# PreAmplicationFilteringCircuit.net
KiCad netlist of a schematic drawn in Altium Designer
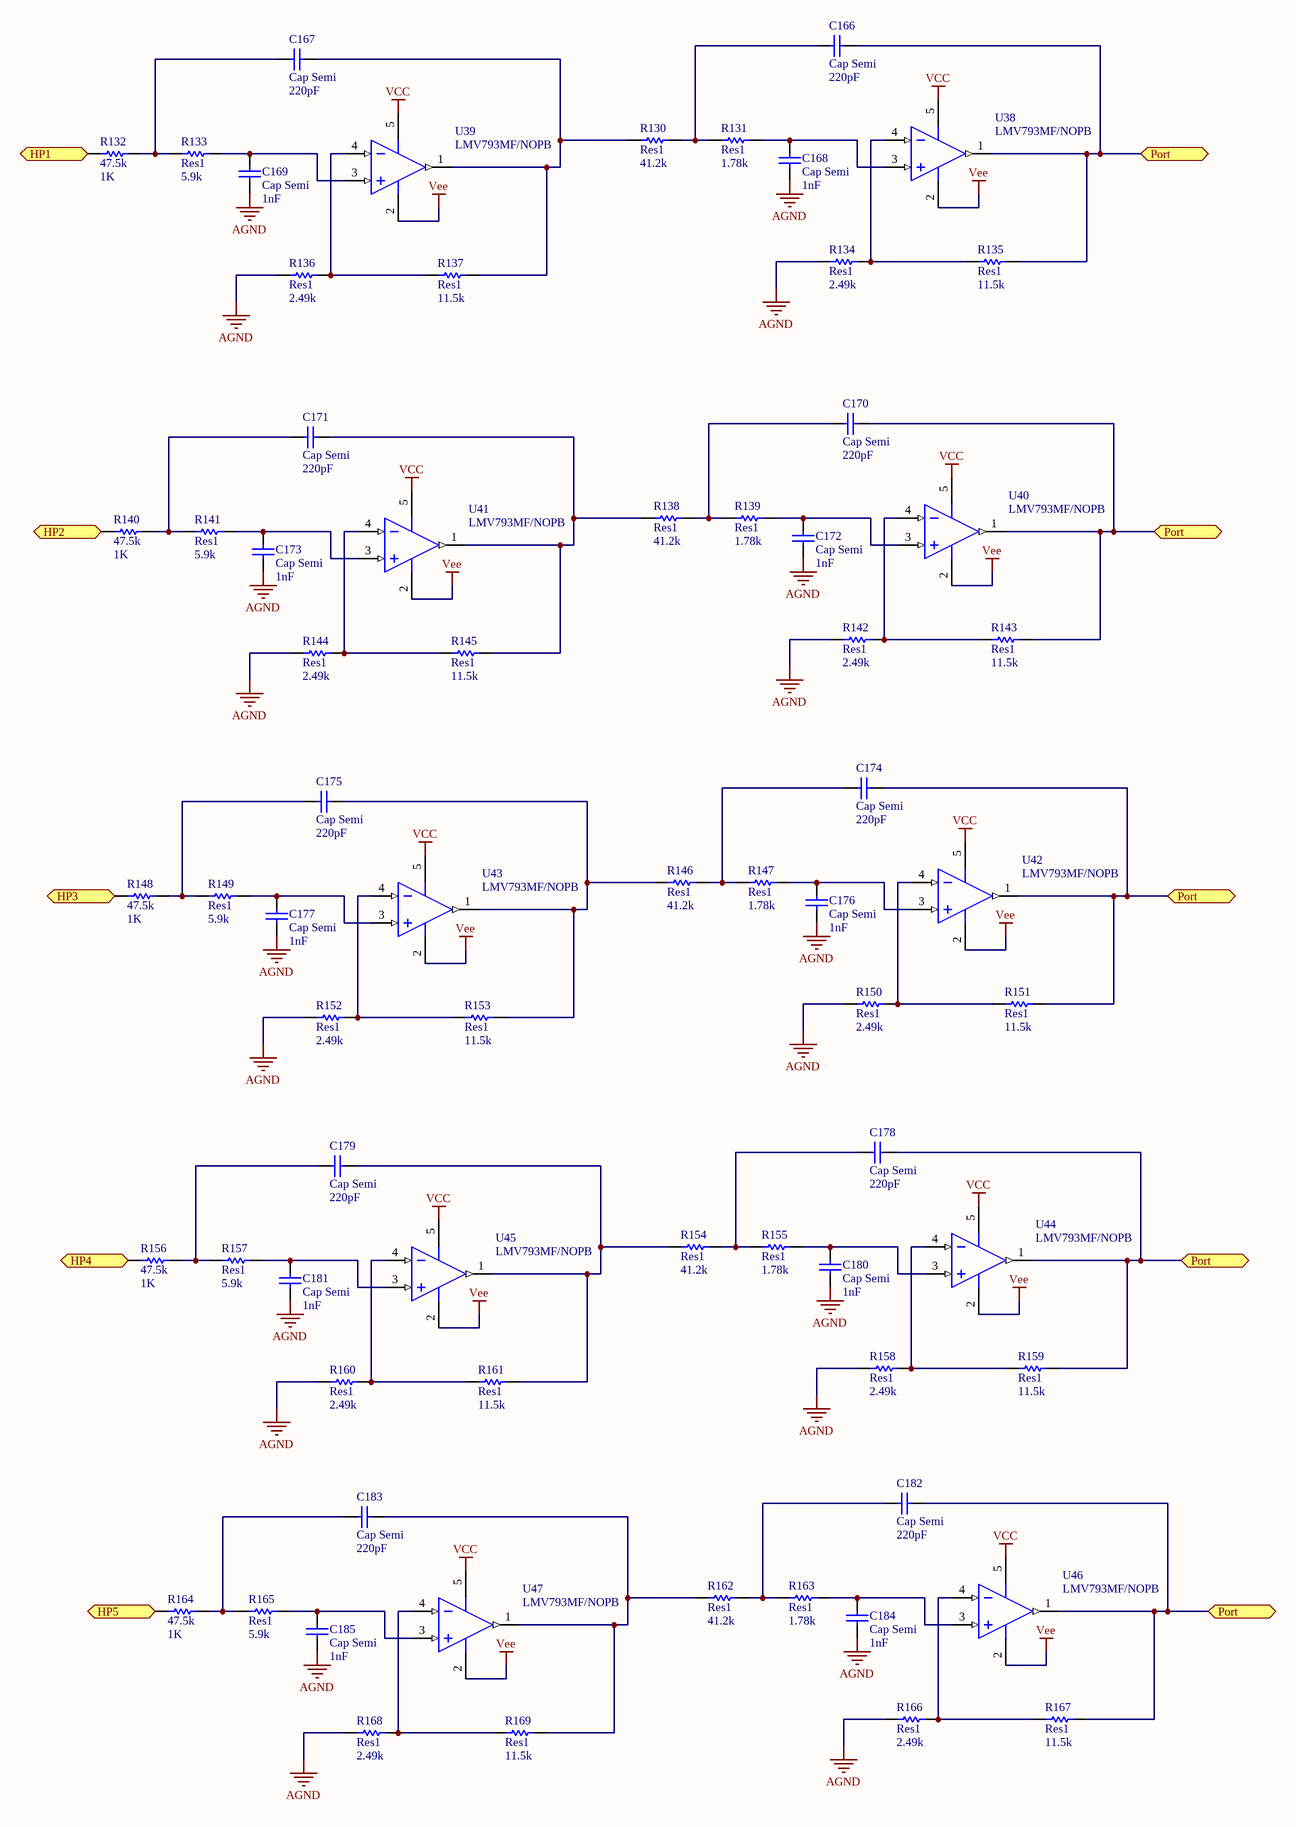
[diagram p0: PreAmplicationFilteringCircuit.SchDoc]

(export (version "E")
  (design (tool "Eeschema 10.0.6"))
  (components
    (comp (ref "C166")
      (value "Cap Semi")
      (footprint "0402")
      (description "Capacitor (Semiconductor SIM Model)")
      (fields (field (name "ALTIUM_VALUE") "220pF") (field (name "PUBLISHER") "Altium Limited"))
      (libsource (lib "Miscellaneous Devices") (part "Cap Semi"))
    )
    (comp (ref "C167")
      (value "Cap Semi")
      (footprint "0402")
      (description "Capacitor (Semiconductor SIM Model)")
      (fields (field (name "ALTIUM_VALUE") "220pF") (field (name "PUBLISHER") "Altium Limited"))
      (libsource (lib "Miscellaneous Devices") (part "Cap Semi"))
    )
    (comp (ref "C168")
      (value "Cap Semi")
      (footprint "0402")
      (description "Capacitor (Semiconductor SIM Model)")
      (fields (field (name "ALTIUM_VALUE") "1nF") (field (name "PUBLISHER") "Altium Limited"))
      (libsource (lib "Miscellaneous Devices") (part "Cap Semi"))
    )
    (comp (ref "C169")
      (value "Cap Semi")
      (footprint "0402")
      (description "Capacitor (Semiconductor SIM Model)")
      (fields (field (name "ALTIUM_VALUE") "1nF") (field (name "PUBLISHER") "Altium Limited"))
      (libsource (lib "Miscellaneous Devices") (part "Cap Semi"))
    )
    (comp (ref "C170")
      (value "Cap Semi")
      (footprint "0402")
      (description "Capacitor (Semiconductor SIM Model)")
      (fields (field (name "ALTIUM_VALUE") "220pF") (field (name "PUBLISHER") "Altium Limited"))
      (libsource (lib "Miscellaneous Devices") (part "Cap Semi"))
    )
    (comp (ref "C171")
      (value "Cap Semi")
      (footprint "0402")
      (description "Capacitor (Semiconductor SIM Model)")
      (fields (field (name "ALTIUM_VALUE") "220pF") (field (name "PUBLISHER") "Altium Limited"))
      (libsource (lib "Miscellaneous Devices") (part "Cap Semi"))
    )
    (comp (ref "C172")
      (value "Cap Semi")
      (footprint "0402")
      (description "Capacitor (Semiconductor SIM Model)")
      (fields (field (name "ALTIUM_VALUE") "1nF") (field (name "PUBLISHER") "Altium Limited"))
      (libsource (lib "Miscellaneous Devices") (part "Cap Semi"))
    )
    (comp (ref "C173")
      (value "Cap Semi")
      (footprint "0402")
      (description "Capacitor (Semiconductor SIM Model)")
      (fields (field (name "ALTIUM_VALUE") "1nF") (field (name "PUBLISHER") "Altium Limited"))
      (libsource (lib "Miscellaneous Devices") (part "Cap Semi"))
    )
    (comp (ref "C174")
      (value "Cap Semi")
      (footprint "0402")
      (description "Capacitor (Semiconductor SIM Model)")
      (fields (field (name "ALTIUM_VALUE") "220pF") (field (name "PUBLISHER") "Altium Limited"))
      (libsource (lib "Miscellaneous Devices") (part "Cap Semi"))
    )
    (comp (ref "C175")
      (value "Cap Semi")
      (footprint "0402")
      (description "Capacitor (Semiconductor SIM Model)")
      (fields (field (name "ALTIUM_VALUE") "220pF") (field (name "PUBLISHER") "Altium Limited"))
      (libsource (lib "Miscellaneous Devices") (part "Cap Semi"))
    )
    (comp (ref "C176")
      (value "Cap Semi")
      (footprint "0402")
      (description "Capacitor (Semiconductor SIM Model)")
      (fields (field (name "ALTIUM_VALUE") "1nF") (field (name "PUBLISHER") "Altium Limited"))
      (libsource (lib "Miscellaneous Devices") (part "Cap Semi"))
    )
    (comp (ref "C177")
      (value "Cap Semi")
      (footprint "0402")
      (description "Capacitor (Semiconductor SIM Model)")
      (fields (field (name "ALTIUM_VALUE") "1nF") (field (name "PUBLISHER") "Altium Limited"))
      (libsource (lib "Miscellaneous Devices") (part "Cap Semi"))
    )
    (comp (ref "C178")
      (value "Cap Semi")
      (footprint "0402")
      (description "Capacitor (Semiconductor SIM Model)")
      (fields (field (name "ALTIUM_VALUE") "220pF") (field (name "PUBLISHER") "Altium Limited"))
      (libsource (lib "Miscellaneous Devices") (part "Cap Semi"))
    )
    (comp (ref "C179")
      (value "Cap Semi")
      (footprint "0402")
      (description "Capacitor (Semiconductor SIM Model)")
      (fields (field (name "ALTIUM_VALUE") "220pF") (field (name "PUBLISHER") "Altium Limited"))
      (libsource (lib "Miscellaneous Devices") (part "Cap Semi"))
    )
    (comp (ref "C180")
      (value "Cap Semi")
      (footprint "0402")
      (description "Capacitor (Semiconductor SIM Model)")
      (fields (field (name "ALTIUM_VALUE") "1nF") (field (name "PUBLISHER") "Altium Limited"))
      (libsource (lib "Miscellaneous Devices") (part "Cap Semi"))
    )
    (comp (ref "C181")
      (value "Cap Semi")
      (footprint "0402")
      (description "Capacitor (Semiconductor SIM Model)")
      (fields (field (name "ALTIUM_VALUE") "1nF") (field (name "PUBLISHER") "Altium Limited"))
      (libsource (lib "Miscellaneous Devices") (part "Cap Semi"))
    )
    (comp (ref "C182")
      (value "Cap Semi")
      (footprint "0402")
      (description "Capacitor (Semiconductor SIM Model)")
      (fields (field (name "ALTIUM_VALUE") "220pF") (field (name "PUBLISHER") "Altium Limited"))
      (libsource (lib "Miscellaneous Devices") (part "Cap Semi"))
    )
    (comp (ref "C183")
      (value "Cap Semi")
      (footprint "0402")
      (description "Capacitor (Semiconductor SIM Model)")
      (fields (field (name "ALTIUM_VALUE") "220pF") (field (name "PUBLISHER") "Altium Limited"))
      (libsource (lib "Miscellaneous Devices") (part "Cap Semi"))
    )
    (comp (ref "C184")
      (value "Cap Semi")
      (footprint "0402")
      (description "Capacitor (Semiconductor SIM Model)")
      (fields (field (name "ALTIUM_VALUE") "1nF") (field (name "PUBLISHER") "Altium Limited"))
      (libsource (lib "Miscellaneous Devices") (part "Cap Semi"))
    )
    (comp (ref "C185")
      (value "Cap Semi")
      (footprint "0402")
      (description "Capacitor (Semiconductor SIM Model)")
      (fields (field (name "ALTIUM_VALUE") "1nF") (field (name "PUBLISHER") "Altium Limited"))
      (libsource (lib "Miscellaneous Devices") (part "Cap Semi"))
    )
    (comp (ref "R130")
      (value "Res1")
      (footprint "AXIAL-0.3")
      (description "Resistor")
      (fields (field (name "ALTIUM_VALUE") "41.2k") (field (name "PUBLISHER") "Altium Limited"))
      (libsource (lib "Miscellaneous Devices") (part "Res1"))
    )
    (comp (ref "R131")
      (value "Res1")
      (footprint "AXIAL-0.3")
      (description "Resistor")
      (fields (field (name "ALTIUM_VALUE") "1.78k") (field (name "PUBLISHER") "Altium Limited"))
      (libsource (lib "Miscellaneous Devices") (part "Res1"))
    )
    (comp (ref "R132")
      (value "47.5k")
      (footprint "AXIAL-0.3")
      (description "Resistor")
      (fields (field (name "ALTIUM_VALUE") "1K") (field (name "PUBLISHER") "Altium Limited"))
      (libsource (lib "Miscellaneous Devices") (part "Res1"))
    )
    (comp (ref "R133")
      (value "Res1")
      (footprint "AXIAL-0.3")
      (description "Resistor")
      (fields (field (name "ALTIUM_VALUE") "5.9k") (field (name "PUBLISHER") "Altium Limited"))
      (libsource (lib "Miscellaneous Devices") (part "Res1"))
    )
    (comp (ref "R134")
      (value "Res1")
      (footprint "AXIAL-0.3")
      (description "Resistor")
      (fields (field (name "ALTIUM_VALUE") "2.49k") (field (name "PUBLISHER") "Altium Limited"))
      (libsource (lib "Miscellaneous Devices") (part "Res1"))
    )
    (comp (ref "R135")
      (value "Res1")
      (footprint "AXIAL-0.3")
      (description "Resistor")
      (fields (field (name "ALTIUM_VALUE") "11.5k") (field (name "PUBLISHER") "Altium Limited"))
      (libsource (lib "Miscellaneous Devices") (part "Res1"))
    )
    (comp (ref "R136")
      (value "Res1")
      (footprint "AXIAL-0.3")
      (description "Resistor")
      (fields (field (name "ALTIUM_VALUE") "2.49k") (field (name "PUBLISHER") "Altium Limited"))
      (libsource (lib "Miscellaneous Devices") (part "Res1"))
    )
    (comp (ref "R137")
      (value "Res1")
      (footprint "AXIAL-0.3")
      (description "Resistor")
      (fields (field (name "ALTIUM_VALUE") "11.5k") (field (name "PUBLISHER") "Altium Limited"))
      (libsource (lib "Miscellaneous Devices") (part "Res1"))
    )
    (comp (ref "R138")
      (value "Res1")
      (footprint "AXIAL-0.3")
      (description "Resistor")
      (fields (field (name "ALTIUM_VALUE") "41.2k") (field (name "PUBLISHER") "Altium Limited"))
      (libsource (lib "Miscellaneous Devices") (part "Res1"))
    )
    (comp (ref "R139")
      (value "Res1")
      (footprint "AXIAL-0.3")
      (description "Resistor")
      (fields (field (name "ALTIUM_VALUE") "1.78k") (field (name "PUBLISHER") "Altium Limited"))
      (libsource (lib "Miscellaneous Devices") (part "Res1"))
    )
    (comp (ref "R140")
      (value "47.5k")
      (footprint "AXIAL-0.3")
      (description "Resistor")
      (fields (field (name "ALTIUM_VALUE") "1K") (field (name "PUBLISHER") "Altium Limited"))
      (libsource (lib "Miscellaneous Devices") (part "Res1"))
    )
    (comp (ref "R141")
      (value "Res1")
      (footprint "AXIAL-0.3")
      (description "Resistor")
      (fields (field (name "ALTIUM_VALUE") "5.9k") (field (name "PUBLISHER") "Altium Limited"))
      (libsource (lib "Miscellaneous Devices") (part "Res1"))
    )
    (comp (ref "R142")
      (value "Res1")
      (footprint "AXIAL-0.3")
      (description "Resistor")
      (fields (field (name "ALTIUM_VALUE") "2.49k") (field (name "PUBLISHER") "Altium Limited"))
      (libsource (lib "Miscellaneous Devices") (part "Res1"))
    )
    (comp (ref "R143")
      (value "Res1")
      (footprint "AXIAL-0.3")
      (description "Resistor")
      (fields (field (name "ALTIUM_VALUE") "11.5k") (field (name "PUBLISHER") "Altium Limited"))
      (libsource (lib "Miscellaneous Devices") (part "Res1"))
    )
    (comp (ref "R144")
      (value "Res1")
      (footprint "AXIAL-0.3")
      (description "Resistor")
      (fields (field (name "ALTIUM_VALUE") "2.49k") (field (name "PUBLISHER") "Altium Limited"))
      (libsource (lib "Miscellaneous Devices") (part "Res1"))
    )
    (comp (ref "R145")
      (value "Res1")
      (footprint "AXIAL-0.3")
      (description "Resistor")
      (fields (field (name "ALTIUM_VALUE") "11.5k") (field (name "PUBLISHER") "Altium Limited"))
      (libsource (lib "Miscellaneous Devices") (part "Res1"))
    )
    (comp (ref "R146")
      (value "Res1")
      (footprint "AXIAL-0.3")
      (description "Resistor")
      (fields (field (name "ALTIUM_VALUE") "41.2k") (field (name "PUBLISHER") "Altium Limited"))
      (libsource (lib "Miscellaneous Devices") (part "Res1"))
    )
    (comp (ref "R147")
      (value "Res1")
      (footprint "AXIAL-0.3")
      (description "Resistor")
      (fields (field (name "ALTIUM_VALUE") "1.78k") (field (name "PUBLISHER") "Altium Limited"))
      (libsource (lib "Miscellaneous Devices") (part "Res1"))
    )
    (comp (ref "R148")
      (value "47.5k")
      (footprint "AXIAL-0.3")
      (description "Resistor")
      (fields (field (name "ALTIUM_VALUE") "1K") (field (name "PUBLISHER") "Altium Limited"))
      (libsource (lib "Miscellaneous Devices") (part "Res1"))
    )
    (comp (ref "R149")
      (value "Res1")
      (footprint "AXIAL-0.3")
      (description "Resistor")
      (fields (field (name "ALTIUM_VALUE") "5.9k") (field (name "PUBLISHER") "Altium Limited"))
      (libsource (lib "Miscellaneous Devices") (part "Res1"))
    )
    (comp (ref "R150")
      (value "Res1")
      (footprint "AXIAL-0.3")
      (description "Resistor")
      (fields (field (name "ALTIUM_VALUE") "2.49k") (field (name "PUBLISHER") "Altium Limited"))
      (libsource (lib "Miscellaneous Devices") (part "Res1"))
    )
    (comp (ref "R151")
      (value "Res1")
      (footprint "AXIAL-0.3")
      (description "Resistor")
      (fields (field (name "ALTIUM_VALUE") "11.5k") (field (name "PUBLISHER") "Altium Limited"))
      (libsource (lib "Miscellaneous Devices") (part "Res1"))
    )
    (comp (ref "R152")
      (value "Res1")
      (footprint "AXIAL-0.3")
      (description "Resistor")
      (fields (field (name "ALTIUM_VALUE") "2.49k") (field (name "PUBLISHER") "Altium Limited"))
      (libsource (lib "Miscellaneous Devices") (part "Res1"))
    )
    (comp (ref "R153")
      (value "Res1")
      (footprint "AXIAL-0.3")
      (description "Resistor")
      (fields (field (name "ALTIUM_VALUE") "11.5k") (field (name "PUBLISHER") "Altium Limited"))
      (libsource (lib "Miscellaneous Devices") (part "Res1"))
    )
    (comp (ref "R154")
      (value "Res1")
      (footprint "AXIAL-0.3")
      (description "Resistor")
      (fields (field (name "ALTIUM_VALUE") "41.2k") (field (name "PUBLISHER") "Altium Limited"))
      (libsource (lib "Miscellaneous Devices") (part "Res1"))
    )
    (comp (ref "R155")
      (value "Res1")
      (footprint "AXIAL-0.3")
      (description "Resistor")
      (fields (field (name "ALTIUM_VALUE") "1.78k") (field (name "PUBLISHER") "Altium Limited"))
      (libsource (lib "Miscellaneous Devices") (part "Res1"))
    )
    (comp (ref "R156")
      (value "47.5k")
      (footprint "AXIAL-0.3")
      (description "Resistor")
      (fields (field (name "ALTIUM_VALUE") "1K") (field (name "PUBLISHER") "Altium Limited"))
      (libsource (lib "Miscellaneous Devices") (part "Res1"))
    )
    (comp (ref "R157")
      (value "Res1")
      (footprint "AXIAL-0.3")
      (description "Resistor")
      (fields (field (name "ALTIUM_VALUE") "5.9k") (field (name "PUBLISHER") "Altium Limited"))
      (libsource (lib "Miscellaneous Devices") (part "Res1"))
    )
    (comp (ref "R158")
      (value "Res1")
      (footprint "AXIAL-0.3")
      (description "Resistor")
      (fields (field (name "ALTIUM_VALUE") "2.49k") (field (name "PUBLISHER") "Altium Limited"))
      (libsource (lib "Miscellaneous Devices") (part "Res1"))
    )
    (comp (ref "R159")
      (value "Res1")
      (footprint "AXIAL-0.3")
      (description "Resistor")
      (fields (field (name "ALTIUM_VALUE") "11.5k") (field (name "PUBLISHER") "Altium Limited"))
      (libsource (lib "Miscellaneous Devices") (part "Res1"))
    )
    (comp (ref "R160")
      (value "Res1")
      (footprint "AXIAL-0.3")
      (description "Resistor")
      (fields (field (name "ALTIUM_VALUE") "2.49k") (field (name "PUBLISHER") "Altium Limited"))
      (libsource (lib "Miscellaneous Devices") (part "Res1"))
    )
    (comp (ref "R161")
      (value "Res1")
      (footprint "AXIAL-0.3")
      (description "Resistor")
      (fields (field (name "ALTIUM_VALUE") "11.5k") (field (name "PUBLISHER") "Altium Limited"))
      (libsource (lib "Miscellaneous Devices") (part "Res1"))
    )
    (comp (ref "R162")
      (value "Res1")
      (footprint "AXIAL-0.3")
      (description "Resistor")
      (fields (field (name "ALTIUM_VALUE") "41.2k") (field (name "PUBLISHER") "Altium Limited"))
      (libsource (lib "Miscellaneous Devices") (part "Res1"))
    )
    (comp (ref "R163")
      (value "Res1")
      (footprint "AXIAL-0.3")
      (description "Resistor")
      (fields (field (name "ALTIUM_VALUE") "1.78k") (field (name "PUBLISHER") "Altium Limited"))
      (libsource (lib "Miscellaneous Devices") (part "Res1"))
    )
    (comp (ref "R164")
      (value "47.5k")
      (footprint "AXIAL-0.3")
      (description "Resistor")
      (fields (field (name "ALTIUM_VALUE") "1K") (field (name "PUBLISHER") "Altium Limited"))
      (libsource (lib "Miscellaneous Devices") (part "Res1"))
    )
    (comp (ref "R165")
      (value "Res1")
      (footprint "AXIAL-0.3")
      (description "Resistor")
      (fields (field (name "ALTIUM_VALUE") "5.9k") (field (name "PUBLISHER") "Altium Limited"))
      (libsource (lib "Miscellaneous Devices") (part "Res1"))
    )
    (comp (ref "R166")
      (value "Res1")
      (footprint "AXIAL-0.3")
      (description "Resistor")
      (fields (field (name "ALTIUM_VALUE") "2.49k") (field (name "PUBLISHER") "Altium Limited"))
      (libsource (lib "Miscellaneous Devices") (part "Res1"))
    )
    (comp (ref "R167")
      (value "Res1")
      (footprint "AXIAL-0.3")
      (description "Resistor")
      (fields (field (name "ALTIUM_VALUE") "11.5k") (field (name "PUBLISHER") "Altium Limited"))
      (libsource (lib "Miscellaneous Devices") (part "Res1"))
    )
    (comp (ref "R168")
      (value "Res1")
      (footprint "AXIAL-0.3")
      (description "Resistor")
      (fields (field (name "ALTIUM_VALUE") "2.49k") (field (name "PUBLISHER") "Altium Limited"))
      (libsource (lib "Miscellaneous Devices") (part "Res1"))
    )
    (comp (ref "R169")
      (value "Res1")
      (footprint "AXIAL-0.3")
      (description "Resistor")
      (fields (field (name "ALTIUM_VALUE") "11.5k") (field (name "PUBLISHER") "Altium Limited"))
      (libsource (lib "Miscellaneous Devices") (part "Res1"))
    )
    (comp (ref "U38")
      (value "LMV793MF/NOPB")
      (footprint "DBV0005A_N")
      (description "88 MHz, Low Noise, 1.8V CMOS Input, Decompensated Operational Amplifiers, 5-pin SOT-23, Pb-Free")
      (fields (field (name "MANUFACTURER") "Texas Instruments"))
      (libsource (lib "Altium Content Vault") (part "AMP-OPA-LM7121-5"))
    )
    (comp (ref "U39")
      (value "LMV793MF/NOPB")
      (footprint "DBV0005A_N")
      (description "88 MHz, Low Noise, 1.8V CMOS Input, Decompensated Operational Amplifiers, 5-pin SOT-23, Pb-Free")
      (fields (field (name "MANUFACTURER") "Texas Instruments"))
      (libsource (lib "Altium Content Vault") (part "AMP-OPA-LM7121-5"))
    )
    (comp (ref "U40")
      (value "LMV793MF/NOPB")
      (footprint "DBV0005A_N")
      (description "88 MHz, Low Noise, 1.8V CMOS Input, Decompensated Operational Amplifiers, 5-pin SOT-23, Pb-Free")
      (fields (field (name "MANUFACTURER") "Texas Instruments"))
      (libsource (lib "Altium Content Vault") (part "AMP-OPA-LM7121-5"))
    )
    (comp (ref "U41")
      (value "LMV793MF/NOPB")
      (footprint "DBV0005A_N")
      (description "88 MHz, Low Noise, 1.8V CMOS Input, Decompensated Operational Amplifiers, 5-pin SOT-23, Pb-Free")
      (fields (field (name "MANUFACTURER") "Texas Instruments"))
      (libsource (lib "Altium Content Vault") (part "AMP-OPA-LM7121-5"))
    )
    (comp (ref "U42")
      (value "LMV793MF/NOPB")
      (footprint "DBV0005A_N")
      (description "88 MHz, Low Noise, 1.8V CMOS Input, Decompensated Operational Amplifiers, 5-pin SOT-23, Pb-Free")
      (fields (field (name "MANUFACTURER") "Texas Instruments"))
      (libsource (lib "Altium Content Vault") (part "AMP-OPA-LM7121-5"))
    )
    (comp (ref "U43")
      (value "LMV793MF/NOPB")
      (footprint "DBV0005A_N")
      (description "88 MHz, Low Noise, 1.8V CMOS Input, Decompensated Operational Amplifiers, 5-pin SOT-23, Pb-Free")
      (fields (field (name "MANUFACTURER") "Texas Instruments"))
      (libsource (lib "Altium Content Vault") (part "AMP-OPA-LM7121-5"))
    )
    (comp (ref "U44")
      (value "LMV793MF/NOPB")
      (footprint "DBV0005A_N")
      (description "88 MHz, Low Noise, 1.8V CMOS Input, Decompensated Operational Amplifiers, 5-pin SOT-23, Pb-Free")
      (fields (field (name "MANUFACTURER") "Texas Instruments"))
      (libsource (lib "Altium Content Vault") (part "AMP-OPA-LM7121-5"))
    )
    (comp (ref "U45")
      (value "LMV793MF/NOPB")
      (footprint "DBV0005A_N")
      (description "88 MHz, Low Noise, 1.8V CMOS Input, Decompensated Operational Amplifiers, 5-pin SOT-23, Pb-Free")
      (fields (field (name "MANUFACTURER") "Texas Instruments"))
      (libsource (lib "Altium Content Vault") (part "AMP-OPA-LM7121-5"))
    )
    (comp (ref "U46")
      (value "LMV793MF/NOPB")
      (footprint "DBV0005A_N")
      (description "88 MHz, Low Noise, 1.8V CMOS Input, Decompensated Operational Amplifiers, 5-pin SOT-23, Pb-Free")
      (fields (field (name "MANUFACTURER") "Texas Instruments"))
      (libsource (lib "Altium Content Vault") (part "AMP-OPA-LM7121-5"))
    )
    (comp (ref "U47")
      (value "LMV793MF/NOPB")
      (footprint "DBV0005A_N")
      (description "88 MHz, Low Noise, 1.8V CMOS Input, Decompensated Operational Amplifiers, 5-pin SOT-23, Pb-Free")
      (fields (field (name "MANUFACTURER") "Texas Instruments"))
      (libsource (lib "Altium Content Vault") (part "AMP-OPA-LM7121-5"))
    )
  )
  (nets
    (net (code "1") (name "/HP1") (class "Default")
      (node (ref "R132") (pin "1") (pinfunction "1_1") (pintype "passive"))
    )
    (net (code "2") (name "/HP2") (class "Default")
      (node (ref "R140") (pin "1") (pinfunction "1_1") (pintype "passive"))
    )
    (net (code "3") (name "/HP3") (class "Default")
      (node (ref "R148") (pin "1") (pinfunction "1_1") (pintype "passive"))
    )
    (net (code "4") (name "/HP4") (class "Default")
      (node (ref "R156") (pin "1") (pinfunction "1_1") (pintype "passive"))
    )
    (net (code "5") (name "/HP5") (class "Default")
      (node (ref "R164") (pin "1") (pinfunction "1_1") (pintype "passive"))
    )
    (net (code "6") (name "/Port") (class "Default")
      (node (ref "C166") (pin "2") (pinfunction "2_2") (pintype "passive"))
      (node (ref "C170") (pin "2") (pinfunction "2_2") (pintype "passive"))
      (node (ref "C174") (pin "2") (pinfunction "2_2") (pintype "passive"))
      (node (ref "C178") (pin "2") (pinfunction "2_2") (pintype "passive"))
      (node (ref "C182") (pin "2") (pinfunction "2_2") (pintype "passive"))
      (node (ref "R135") (pin "2") (pinfunction "2_2") (pintype "passive"))
      (node (ref "R143") (pin "2") (pinfunction "2_2") (pintype "passive"))
      (node (ref "R151") (pin "2") (pinfunction "2_2") (pintype "passive"))
      (node (ref "R159") (pin "2") (pinfunction "2_2") (pintype "passive"))
      (node (ref "R167") (pin "2") (pinfunction "2_2") (pintype "passive"))
      (node (ref "U38") (pin "1") (pinfunction "OUT_1") (pintype "output"))
      (node (ref "U40") (pin "1") (pinfunction "OUT_1") (pintype "output"))
      (node (ref "U42") (pin "1") (pinfunction "OUT_1") (pintype "output"))
      (node (ref "U44") (pin "1") (pinfunction "OUT_1") (pintype "output"))
      (node (ref "U46") (pin "1") (pinfunction "OUT_1") (pintype "output"))
    )
    (net (code "7") (name "AGND") (class "Default")
      (node (ref "C168") (pin "1") (pinfunction "1_1") (pintype "passive"))
      (node (ref "C169") (pin "1") (pinfunction "1_1") (pintype "passive"))
      (node (ref "C172") (pin "1") (pinfunction "1_1") (pintype "passive"))
      (node (ref "C173") (pin "1") (pinfunction "1_1") (pintype "passive"))
      (node (ref "C176") (pin "1") (pinfunction "1_1") (pintype "passive"))
      (node (ref "C177") (pin "1") (pinfunction "1_1") (pintype "passive"))
      (node (ref "C180") (pin "1") (pinfunction "1_1") (pintype "passive"))
      (node (ref "C181") (pin "1") (pinfunction "1_1") (pintype "passive"))
      (node (ref "C184") (pin "1") (pinfunction "1_1") (pintype "passive"))
      (node (ref "C185") (pin "1") (pinfunction "1_1") (pintype "passive"))
      (node (ref "R134") (pin "1") (pinfunction "1_1") (pintype "passive"))
      (node (ref "R136") (pin "1") (pinfunction "1_1") (pintype "passive"))
      (node (ref "R142") (pin "1") (pinfunction "1_1") (pintype "passive"))
      (node (ref "R144") (pin "1") (pinfunction "1_1") (pintype "passive"))
      (node (ref "R150") (pin "1") (pinfunction "1_1") (pintype "passive"))
      (node (ref "R152") (pin "1") (pinfunction "1_1") (pintype "passive"))
      (node (ref "R158") (pin "1") (pinfunction "1_1") (pintype "passive"))
      (node (ref "R160") (pin "1") (pinfunction "1_1") (pintype "passive"))
      (node (ref "R166") (pin "1") (pinfunction "1_1") (pintype "passive"))
      (node (ref "R168") (pin "1") (pinfunction "1_1") (pintype "passive"))
    )
    (net (code "8") (name "Net-(C166-Pad1)") (class "Default")
      (node (ref "C166") (pin "1") (pinfunction "1_1") (pintype "passive"))
      (node (ref "R130") (pin "2") (pinfunction "2_2") (pintype "passive"))
      (node (ref "R131") (pin "1") (pinfunction "1_1") (pintype "passive"))
    )
    (net (code "9") (name "Net-(C167-Pad1)") (class "Default")
      (node (ref "C167") (pin "1") (pinfunction "1_1") (pintype "passive"))
      (node (ref "R132") (pin "2") (pinfunction "2_2") (pintype "passive"))
      (node (ref "R133") (pin "1") (pinfunction "1_1") (pintype "passive"))
    )
    (net (code "10") (name "Net-(C170-Pad1)") (class "Default")
      (node (ref "C170") (pin "1") (pinfunction "1_1") (pintype "passive"))
      (node (ref "R138") (pin "2") (pinfunction "2_2") (pintype "passive"))
      (node (ref "R139") (pin "1") (pinfunction "1_1") (pintype "passive"))
    )
    (net (code "11") (name "Net-(C171-Pad1)") (class "Default")
      (node (ref "C171") (pin "1") (pinfunction "1_1") (pintype "passive"))
      (node (ref "R140") (pin "2") (pinfunction "2_2") (pintype "passive"))
      (node (ref "R141") (pin "1") (pinfunction "1_1") (pintype "passive"))
    )
    (net (code "12") (name "Net-(C174-Pad1)") (class "Default")
      (node (ref "C174") (pin "1") (pinfunction "1_1") (pintype "passive"))
      (node (ref "R146") (pin "2") (pinfunction "2_2") (pintype "passive"))
      (node (ref "R147") (pin "1") (pinfunction "1_1") (pintype "passive"))
    )
    (net (code "13") (name "Net-(C175-Pad1)") (class "Default")
      (node (ref "C175") (pin "1") (pinfunction "1_1") (pintype "passive"))
      (node (ref "R148") (pin "2") (pinfunction "2_2") (pintype "passive"))
      (node (ref "R149") (pin "1") (pinfunction "1_1") (pintype "passive"))
    )
    (net (code "14") (name "Net-(C178-Pad1)") (class "Default")
      (node (ref "C178") (pin "1") (pinfunction "1_1") (pintype "passive"))
      (node (ref "R154") (pin "2") (pinfunction "2_2") (pintype "passive"))
      (node (ref "R155") (pin "1") (pinfunction "1_1") (pintype "passive"))
    )
    (net (code "15") (name "Net-(C179-Pad1)") (class "Default")
      (node (ref "C179") (pin "1") (pinfunction "1_1") (pintype "passive"))
      (node (ref "R156") (pin "2") (pinfunction "2_2") (pintype "passive"))
      (node (ref "R157") (pin "1") (pinfunction "1_1") (pintype "passive"))
    )
    (net (code "16") (name "Net-(C182-Pad1)") (class "Default")
      (node (ref "C182") (pin "1") (pinfunction "1_1") (pintype "passive"))
      (node (ref "R162") (pin "2") (pinfunction "2_2") (pintype "passive"))
      (node (ref "R163") (pin "1") (pinfunction "1_1") (pintype "passive"))
    )
    (net (code "17") (name "Net-(C183-Pad1)") (class "Default")
      (node (ref "C183") (pin "1") (pinfunction "1_1") (pintype "passive"))
      (node (ref "R164") (pin "2") (pinfunction "2_2") (pintype "passive"))
      (node (ref "R165") (pin "1") (pinfunction "1_1") (pintype "passive"))
    )
    (net (code "18") (name "Net-(U38-IN+)") (class "Default")
      (node (ref "C168") (pin "2") (pinfunction "2_2") (pintype "passive"))
      (node (ref "R131") (pin "2") (pinfunction "2_2") (pintype "passive"))
      (node (ref "U38") (pin "3") (pinfunction "IN+_3") (pintype "input"))
    )
    (net (code "19") (name "Net-(U38-IN-)") (class "Default")
      (node (ref "R134") (pin "2") (pinfunction "2_2") (pintype "passive"))
      (node (ref "R135") (pin "1") (pinfunction "1_1") (pintype "passive"))
      (node (ref "U38") (pin "4") (pinfunction "IN-_4") (pintype "input"))
    )
    (net (code "20") (name "Net-(U39-IN+)") (class "Default")
      (node (ref "C169") (pin "2") (pinfunction "2_2") (pintype "passive"))
      (node (ref "R133") (pin "2") (pinfunction "2_2") (pintype "passive"))
      (node (ref "U39") (pin "3") (pinfunction "IN+_3") (pintype "input"))
    )
    (net (code "21") (name "Net-(U39-IN-)") (class "Default")
      (node (ref "R136") (pin "2") (pinfunction "2_2") (pintype "passive"))
      (node (ref "R137") (pin "1") (pinfunction "1_1") (pintype "passive"))
      (node (ref "U39") (pin "4") (pinfunction "IN-_4") (pintype "input"))
    )
    (net (code "22") (name "Net-(U39-OUT)") (class "Default")
      (node (ref "C167") (pin "2") (pinfunction "2_2") (pintype "passive"))
      (node (ref "R130") (pin "1") (pinfunction "1_1") (pintype "passive"))
      (node (ref "R137") (pin "2") (pinfunction "2_2") (pintype "passive"))
      (node (ref "U39") (pin "1") (pinfunction "OUT_1") (pintype "output"))
    )
    (net (code "23") (name "Net-(U40-IN+)") (class "Default")
      (node (ref "C172") (pin "2") (pinfunction "2_2") (pintype "passive"))
      (node (ref "R139") (pin "2") (pinfunction "2_2") (pintype "passive"))
      (node (ref "U40") (pin "3") (pinfunction "IN+_3") (pintype "input"))
    )
    (net (code "24") (name "Net-(U40-IN-)") (class "Default")
      (node (ref "R142") (pin "2") (pinfunction "2_2") (pintype "passive"))
      (node (ref "R143") (pin "1") (pinfunction "1_1") (pintype "passive"))
      (node (ref "U40") (pin "4") (pinfunction "IN-_4") (pintype "input"))
    )
    (net (code "25") (name "Net-(U41-IN+)") (class "Default")
      (node (ref "C173") (pin "2") (pinfunction "2_2") (pintype "passive"))
      (node (ref "R141") (pin "2") (pinfunction "2_2") (pintype "passive"))
      (node (ref "U41") (pin "3") (pinfunction "IN+_3") (pintype "input"))
    )
    (net (code "26") (name "Net-(U41-IN-)") (class "Default")
      (node (ref "R144") (pin "2") (pinfunction "2_2") (pintype "passive"))
      (node (ref "R145") (pin "1") (pinfunction "1_1") (pintype "passive"))
      (node (ref "U41") (pin "4") (pinfunction "IN-_4") (pintype "input"))
    )
    (net (code "27") (name "Net-(U41-OUT)") (class "Default")
      (node (ref "C171") (pin "2") (pinfunction "2_2") (pintype "passive"))
      (node (ref "R138") (pin "1") (pinfunction "1_1") (pintype "passive"))
      (node (ref "R145") (pin "2") (pinfunction "2_2") (pintype "passive"))
      (node (ref "U41") (pin "1") (pinfunction "OUT_1") (pintype "output"))
    )
    (net (code "28") (name "Net-(U42-IN+)") (class "Default")
      (node (ref "C176") (pin "2") (pinfunction "2_2") (pintype "passive"))
      (node (ref "R147") (pin "2") (pinfunction "2_2") (pintype "passive"))
      (node (ref "U42") (pin "3") (pinfunction "IN+_3") (pintype "input"))
    )
    (net (code "29") (name "Net-(U42-IN-)") (class "Default")
      (node (ref "R150") (pin "2") (pinfunction "2_2") (pintype "passive"))
      (node (ref "R151") (pin "1") (pinfunction "1_1") (pintype "passive"))
      (node (ref "U42") (pin "4") (pinfunction "IN-_4") (pintype "input"))
    )
    (net (code "30") (name "Net-(U43-IN+)") (class "Default")
      (node (ref "C177") (pin "2") (pinfunction "2_2") (pintype "passive"))
      (node (ref "R149") (pin "2") (pinfunction "2_2") (pintype "passive"))
      (node (ref "U43") (pin "3") (pinfunction "IN+_3") (pintype "input"))
    )
    (net (code "31") (name "Net-(U43-IN-)") (class "Default")
      (node (ref "R152") (pin "2") (pinfunction "2_2") (pintype "passive"))
      (node (ref "R153") (pin "1") (pinfunction "1_1") (pintype "passive"))
      (node (ref "U43") (pin "4") (pinfunction "IN-_4") (pintype "input"))
    )
    (net (code "32") (name "Net-(U43-OUT)") (class "Default")
      (node (ref "C175") (pin "2") (pinfunction "2_2") (pintype "passive"))
      (node (ref "R146") (pin "1") (pinfunction "1_1") (pintype "passive"))
      (node (ref "R153") (pin "2") (pinfunction "2_2") (pintype "passive"))
      (node (ref "U43") (pin "1") (pinfunction "OUT_1") (pintype "output"))
    )
    (net (code "33") (name "Net-(U44-IN+)") (class "Default")
      (node (ref "C180") (pin "2") (pinfunction "2_2") (pintype "passive"))
      (node (ref "R155") (pin "2") (pinfunction "2_2") (pintype "passive"))
      (node (ref "U44") (pin "3") (pinfunction "IN+_3") (pintype "input"))
    )
    (net (code "34") (name "Net-(U44-IN-)") (class "Default")
      (node (ref "R158") (pin "2") (pinfunction "2_2") (pintype "passive"))
      (node (ref "R159") (pin "1") (pinfunction "1_1") (pintype "passive"))
      (node (ref "U44") (pin "4") (pinfunction "IN-_4") (pintype "input"))
    )
    (net (code "35") (name "Net-(U45-IN+)") (class "Default")
      (node (ref "C181") (pin "2") (pinfunction "2_2") (pintype "passive"))
      (node (ref "R157") (pin "2") (pinfunction "2_2") (pintype "passive"))
      (node (ref "U45") (pin "3") (pinfunction "IN+_3") (pintype "input"))
    )
    (net (code "36") (name "Net-(U45-IN-)") (class "Default")
      (node (ref "R160") (pin "2") (pinfunction "2_2") (pintype "passive"))
      (node (ref "R161") (pin "1") (pinfunction "1_1") (pintype "passive"))
      (node (ref "U45") (pin "4") (pinfunction "IN-_4") (pintype "input"))
    )
    (net (code "37") (name "Net-(U45-OUT)") (class "Default")
      (node (ref "C179") (pin "2") (pinfunction "2_2") (pintype "passive"))
      (node (ref "R154") (pin "1") (pinfunction "1_1") (pintype "passive"))
      (node (ref "R161") (pin "2") (pinfunction "2_2") (pintype "passive"))
      (node (ref "U45") (pin "1") (pinfunction "OUT_1") (pintype "output"))
    )
    (net (code "38") (name "Net-(U46-IN+)") (class "Default")
      (node (ref "C184") (pin "2") (pinfunction "2_2") (pintype "passive"))
      (node (ref "R163") (pin "2") (pinfunction "2_2") (pintype "passive"))
      (node (ref "U46") (pin "3") (pinfunction "IN+_3") (pintype "input"))
    )
    (net (code "39") (name "Net-(U46-IN-)") (class "Default")
      (node (ref "R166") (pin "2") (pinfunction "2_2") (pintype "passive"))
      (node (ref "R167") (pin "1") (pinfunction "1_1") (pintype "passive"))
      (node (ref "U46") (pin "4") (pinfunction "IN-_4") (pintype "input"))
    )
    (net (code "40") (name "Net-(U47-IN+)") (class "Default")
      (node (ref "C185") (pin "2") (pinfunction "2_2") (pintype "passive"))
      (node (ref "R165") (pin "2") (pinfunction "2_2") (pintype "passive"))
      (node (ref "U47") (pin "3") (pinfunction "IN+_3") (pintype "input"))
    )
    (net (code "41") (name "Net-(U47-IN-)") (class "Default")
      (node (ref "R168") (pin "2") (pinfunction "2_2") (pintype "passive"))
      (node (ref "R169") (pin "1") (pinfunction "1_1") (pintype "passive"))
      (node (ref "U47") (pin "4") (pinfunction "IN-_4") (pintype "input"))
    )
    (net (code "42") (name "Net-(U47-OUT)") (class "Default")
      (node (ref "C183") (pin "2") (pinfunction "2_2") (pintype "passive"))
      (node (ref "R162") (pin "1") (pinfunction "1_1") (pintype "passive"))
      (node (ref "R169") (pin "2") (pinfunction "2_2") (pintype "passive"))
      (node (ref "U47") (pin "1") (pinfunction "OUT_1") (pintype "output"))
    )
    (net (code "43") (name "VCC") (class "Default")
      (node (ref "U38") (pin "5") (pinfunction "V+_5") (pintype "power_in"))
      (node (ref "U39") (pin "5") (pinfunction "V+_5") (pintype "power_in"))
      (node (ref "U40") (pin "5") (pinfunction "V+_5") (pintype "power_in"))
      (node (ref "U41") (pin "5") (pinfunction "V+_5") (pintype "power_in"))
      (node (ref "U42") (pin "5") (pinfunction "V+_5") (pintype "power_in"))
      (node (ref "U43") (pin "5") (pinfunction "V+_5") (pintype "power_in"))
      (node (ref "U44") (pin "5") (pinfunction "V+_5") (pintype "power_in"))
      (node (ref "U45") (pin "5") (pinfunction "V+_5") (pintype "power_in"))
      (node (ref "U46") (pin "5") (pinfunction "V+_5") (pintype "power_in"))
      (node (ref "U47") (pin "5") (pinfunction "V+_5") (pintype "power_in"))
    )
    (net (code "44") (name "Vee") (class "Default")
      (node (ref "U38") (pin "2") (pinfunction "V-_2") (pintype "power_in"))
      (node (ref "U39") (pin "2") (pinfunction "V-_2") (pintype "power_in"))
      (node (ref "U40") (pin "2") (pinfunction "V-_2") (pintype "power_in"))
      (node (ref "U41") (pin "2") (pinfunction "V-_2") (pintype "power_in"))
      (node (ref "U42") (pin "2") (pinfunction "V-_2") (pintype "power_in"))
      (node (ref "U43") (pin "2") (pinfunction "V-_2") (pintype "power_in"))
      (node (ref "U44") (pin "2") (pinfunction "V-_2") (pintype "power_in"))
      (node (ref "U45") (pin "2") (pinfunction "V-_2") (pintype "power_in"))
      (node (ref "U46") (pin "2") (pinfunction "V-_2") (pintype "power_in"))
      (node (ref "U47") (pin "2") (pinfunction "V-_2") (pintype "power_in"))
    )
  )
)
